# E-pico.net
KiCad netlist of a schematic drawn in Altium Designer
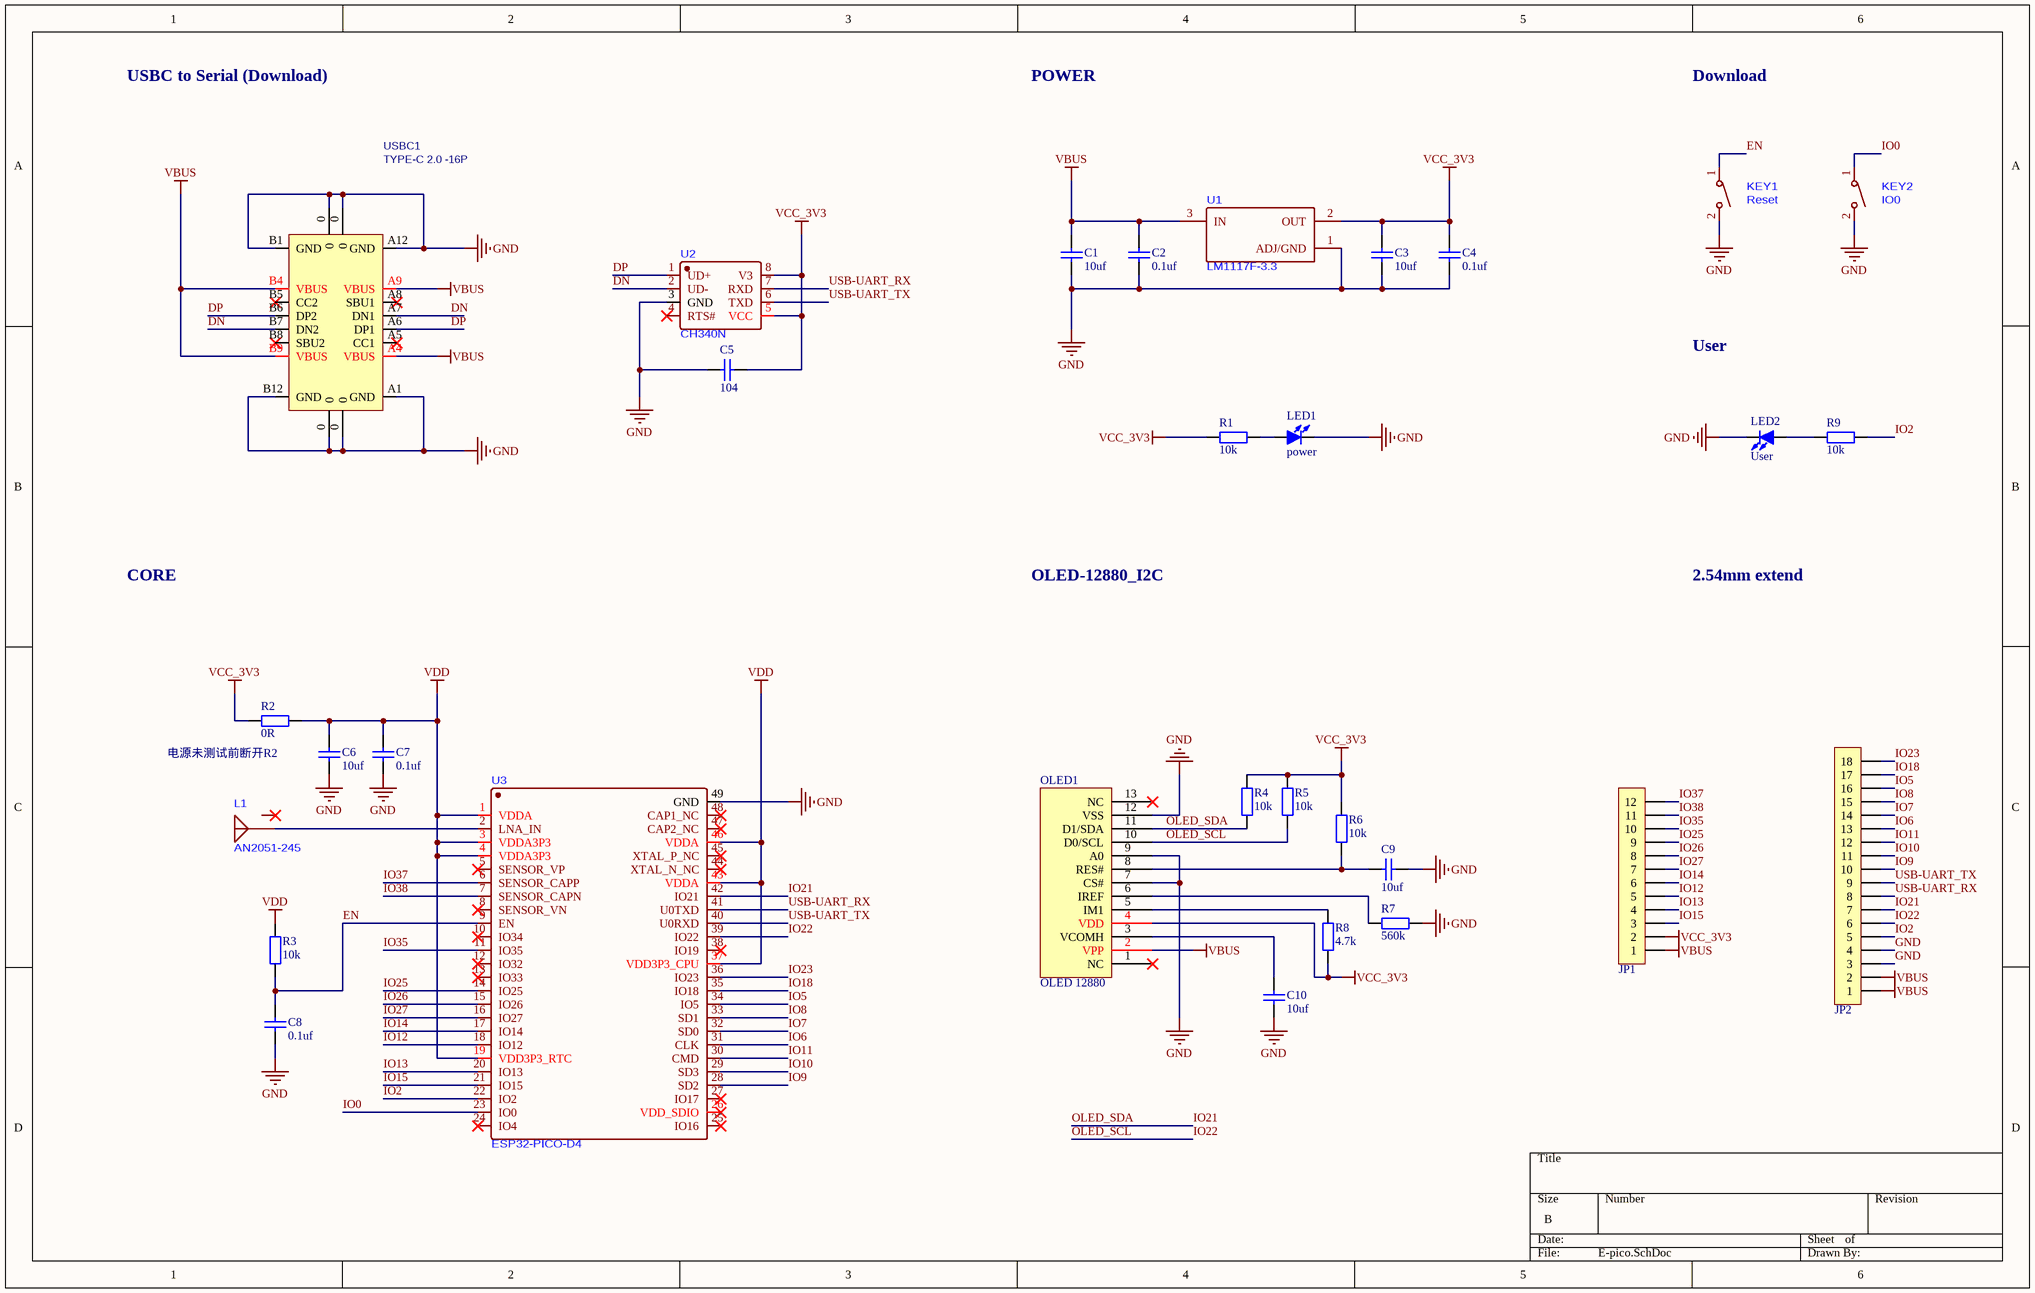
[diagram p0: E-pico.SchDoc]

(export (version "E")
  (design (tool "Eeschema 10.0.6"))
  (components
    (comp (ref "C1")
      (value "10uf")
      (footprint "C0603_M")
      (description "贴片电容/MLCC电容")
      (libsource (lib "0.1 - 电阻-电容-电感-晶振-晶体-磁珠-电位器-法拉电容-馈通电容") (part "C"))
    )
    (comp (ref "C2")
      (value "0.1uf")
      (footprint "C0603_M")
      (description "贴片电容/MLCC电容")
      (libsource (lib "0.1 - 电阻-电容-电感-晶振-晶体-磁珠-电位器-法拉电容-馈通电容") (part "C"))
    )
    (comp (ref "C3")
      (value "10uf")
      (footprint "C0603_M")
      (description "贴片电容/MLCC电容")
      (libsource (lib "0.1 - 电阻-电容-电感-晶振-晶体-磁珠-电位器-法拉电容-馈通电容") (part "C"))
    )
    (comp (ref "C4")
      (value "0.1uf")
      (footprint "C0603_M")
      (description "贴片电容/MLCC电容")
      (libsource (lib "0.1 - 电阻-电容-电感-晶振-晶体-磁珠-电位器-法拉电容-馈通电容") (part "C"))
    )
    (comp (ref "C5")
      (value "104")
      (footprint "C0603_M")
      (description "贴片电容/MLCC电容")
      (libsource (lib "0.1 - 电阻-电容-电感-晶振-晶体-磁珠-电位器-法拉电容-馈通电容") (part "C"))
    )
    (comp (ref "C6")
      (value "10uf")
      (footprint "C0603_M")
      (description "贴片电容/MLCC电容")
      (libsource (lib "0.1 - 电阻-电容-电感-晶振-晶体-磁珠-电位器-法拉电容-馈通电容") (part "C"))
    )
    (comp (ref "C7")
      (value "0.1uf")
      (footprint "C0603_M")
      (description "贴片电容/MLCC电容")
      (libsource (lib "0.1 - 电阻-电容-电感-晶振-晶体-磁珠-电位器-法拉电容-馈通电容") (part "C"))
    )
    (comp (ref "C8")
      (value "0.1uf")
      (footprint "C0603_M")
      (description "贴片电容/MLCC电容")
      (libsource (lib "0.1 - 电阻-电容-电感-晶振-晶体-磁珠-电位器-法拉电容-馈通电容") (part "C"))
    )
    (comp (ref "C9")
      (value "10uf")
      (footprint "C0603_M")
      (description "贴片电容/MLCC电容")
      (libsource (lib "0.1 - 电阻-电容-电感-晶振-晶体-磁珠-电位器-法拉电容-馈通电容") (part "C"))
    )
    (comp (ref "C10")
      (value "10uf")
      (footprint "C0603_M")
      (description "贴片电容/MLCC电容")
      (libsource (lib "0.1 - 电阻-电容-电感-晶振-晶体-磁珠-电位器-法拉电容-馈通电容") (part "C"))
    )
    (comp (ref "JP1")
      (value "HDR-1X12")
      (footprint "HDR2.54-LI-12P")
      (description "12P接插件")
      (libsource (lib "5.5 - 2.54mm连接器(KF2EDGK_XH2.54_2.54排针排母)") (part "Header 12"))
    )
    (comp (ref "JP2")
      (value "HDR-1X18")
      (footprint "HDR2.54-LI-18P")
      (description "18P接插件")
      (libsource (lib "5.5 - 2.54mm连接器(KF2EDGK_XH2.54_2.54排针排母)") (part "Header 18"))
    )
    (comp (ref "KEY1")
      (value "Reset")
      (footprint "SW-SMD_ST-1186S")
      (description "C589199")
      (libsource (lib "E-pico") (part "侧按小龟ST-1186S"))
    )
    (comp (ref "KEY2")
      (value "IO0")
      (footprint "SW-SMD_ST-1186S")
      (description "C589199")
      (libsource (lib "E-pico") (part "侧按小龟ST-1186S"))
    )
    (comp (ref "L1")
      (value "AN2051-245")
      (footprint "ANT2051")
      (libsource (lib "E-pico") (part "AN2051-245"))
    )
    (comp (ref "LED1")
      (value "power")
      (footprint "LED0603_Y")
      (description "贴片LED")
      (libsource (lib "0.3 - LED发光二极管-IR二极管_接收管-光耦") (part "LED-SMD"))
    )
    (comp (ref "LED2")
      (value "User")
      (footprint "LED0603_Y")
      (description "贴片LED")
      (libsource (lib "0.3 - LED发光二极管-IR二极管_接收管-光耦") (part "LED-SMD"))
    )
    (comp (ref "OLED1")
      (value "OLED 12880")
      (footprint "0.78'OLED-12880-13pin-short")
      (libsource (lib "E-pico") (part "0.78寸12880oled"))
    )
    (comp (ref "R1")
      (value "10k")
      (footprint "R0603_M")
      (description "贴片电阻")
      (libsource (lib "0.1 - 电阻-电容-电感-晶振-晶体-磁珠-电位器-法拉电容-馈通电容") (part "R"))
    )
    (comp (ref "R2")
      (value "0R")
      (footprint "R0603_M")
      (description "贴片电阻")
      (libsource (lib "0.1 - 电阻-电容-电感-晶振-晶体-磁珠-电位器-法拉电容-馈通电容") (part "R"))
    )
    (comp (ref "R3")
      (value "10k")
      (footprint "R0603_M")
      (description "贴片电阻")
      (libsource (lib "0.1 - 电阻-电容-电感-晶振-晶体-磁珠-电位器-法拉电容-馈通电容") (part "R"))
    )
    (comp (ref "R4")
      (value "10k")
      (footprint "R0603_M")
      (description "贴片电阻")
      (libsource (lib "0.1 - 电阻-电容-电感-晶振-晶体-磁珠-电位器-法拉电容-馈通电容") (part "R"))
    )
    (comp (ref "R5")
      (value "10k")
      (footprint "R0603_M")
      (description "贴片电阻")
      (libsource (lib "0.1 - 电阻-电容-电感-晶振-晶体-磁珠-电位器-法拉电容-馈通电容") (part "R"))
    )
    (comp (ref "R6")
      (value "10k")
      (footprint "R0603_M")
      (description "贴片电阻")
      (libsource (lib "0.1 - 电阻-电容-电感-晶振-晶体-磁珠-电位器-法拉电容-馈通电容") (part "R"))
    )
    (comp (ref "R7")
      (value "560k")
      (footprint "R0603_M")
      (description "贴片电阻")
      (libsource (lib "0.1 - 电阻-电容-电感-晶振-晶体-磁珠-电位器-法拉电容-馈通电容") (part "R"))
    )
    (comp (ref "R8")
      (value "4.7k")
      (footprint "R0603_M")
      (description "贴片电阻")
      (libsource (lib "0.1 - 电阻-电容-电感-晶振-晶体-磁珠-电位器-法拉电容-馈通电容") (part "R"))
    )
    (comp (ref "R9")
      (value "10k")
      (footprint "R0603_M")
      (description "贴片电阻")
      (libsource (lib "0.1 - 电阻-电容-电感-晶振-晶体-磁珠-电位器-法拉电容-馈通电容") (part "R"))
    )
    (comp (ref "U1")
      (value "LM1117F-3.3")
      (footprint "SOT89-150P410X160-3N")
      (libsource (lib "E-pico") (part "LM1117F-3.3"))
    )
    (comp (ref "U2")
      (value "CH340N")
      (footprint "SOP-8_L5.0-W4.0-P1.27-LS6.0-BL")
      (libsource (lib "E-pico") (part "CH340N"))
    )
    (comp (ref "U3")
      (value "ESP32-PICO-D4")
      (footprint "QFN-48_L7.0-W7.0-P0.50-BL-EP5.4")
      (libsource (lib "E-pico") (part "ESP32-PICO-D4"))
    )
    (comp (ref "USBC1")
      (value "TYPE-C 2.0 -16P")
      (footprint "USB-C-SMD_16P")
      (description "USB2.0_Type-C_16Pin母座")
      (libsource (lib "0.6 - 电源-以太网-音频-Type-C USB插座") (part "USB2.0_Type-C_16Pin"))
    )
  )
  (nets
    (net (code "1") (name "/DN") (class "Default")
      (node (ref "U2") (pin "2") (pinfunction "UD-_2") (pintype "passive"))
      (node (ref "USBC1") (pin "A7") (pinfunction "DN1_A7") (pintype "passive"))
      (node (ref "USBC1") (pin "B7") (pinfunction "DN2_B7") (pintype "passive"))
    )
    (net (code "2") (name "/DP") (class "Default")
      (node (ref "U2") (pin "1") (pinfunction "UD+_1") (pintype "passive"))
      (node (ref "USBC1") (pin "A6") (pinfunction "DP1_A6") (pintype "passive"))
      (node (ref "USBC1") (pin "B6") (pinfunction "DP2_B6") (pintype "passive"))
    )
    (net (code "3") (name "/EN") (class "Default")
      (node (ref "C8") (pin "2") (pinfunction "2_2") (pintype "passive"))
      (node (ref "KEY1") (pin "1") (pinfunction "1_1") (pintype "passive"))
      (node (ref "R3") (pin "2") (pinfunction "2_2") (pintype "passive"))
      (node (ref "U3") (pin "9") (pinfunction "EN_9") (pintype "passive"))
    )
    (net (code "4") (name "/IO0") (class "Default")
      (node (ref "KEY2") (pin "1") (pinfunction "1_1") (pintype "passive"))
      (node (ref "U3") (pin "23") (pinfunction "IO0_23") (pintype "passive"))
    )
    (net (code "5") (name "/IO2") (class "Default")
      (node (ref "JP2") (pin "5") (pinfunction "5_5") (pintype "passive"))
      (node (ref "R9") (pin "1") (pinfunction "1_1") (pintype "passive"))
      (node (ref "U3") (pin "22") (pinfunction "IO2_22") (pintype "passive"))
    )
    (net (code "6") (name "/IO5") (class "Default")
      (node (ref "JP2") (pin "16") (pinfunction "16_16") (pintype "passive"))
      (node (ref "U3") (pin "34") (pinfunction "IO5_34") (pintype "passive"))
    )
    (net (code "7") (name "/IO6") (class "Default")
      (node (ref "JP2") (pin "13") (pinfunction "13_13") (pintype "passive"))
      (node (ref "U3") (pin "31") (pinfunction "CLK_31") (pintype "passive"))
    )
    (net (code "8") (name "/IO7") (class "Default")
      (node (ref "JP2") (pin "14") (pinfunction "14_14") (pintype "passive"))
      (node (ref "U3") (pin "32") (pinfunction "SD0_32") (pintype "passive"))
    )
    (net (code "9") (name "/IO8") (class "Default")
      (node (ref "JP2") (pin "15") (pinfunction "15_15") (pintype "passive"))
      (node (ref "U3") (pin "33") (pinfunction "SD1_33") (pintype "passive"))
    )
    (net (code "10") (name "/IO9") (class "Default")
      (node (ref "JP2") (pin "10") (pinfunction "10_10") (pintype "passive"))
      (node (ref "U3") (pin "28") (pinfunction "SD2_28") (pintype "passive"))
    )
    (net (code "11") (name "/IO10") (class "Default")
      (node (ref "JP2") (pin "11") (pinfunction "11_11") (pintype "passive"))
      (node (ref "U3") (pin "29") (pinfunction "SD3_29") (pintype "passive"))
    )
    (net (code "12") (name "/IO11") (class "Default")
      (node (ref "JP2") (pin "12") (pinfunction "12_12") (pintype "passive"))
      (node (ref "U3") (pin "30") (pinfunction "CMD_30") (pintype "passive"))
    )
    (net (code "13") (name "/IO12") (class "Default")
      (node (ref "JP1") (pin "5") (pinfunction "5_5") (pintype "passive"))
      (node (ref "U3") (pin "18") (pinfunction "IO12_18") (pintype "passive"))
    )
    (net (code "14") (name "/IO13") (class "Default")
      (node (ref "JP1") (pin "4") (pinfunction "4_4") (pintype "passive"))
      (node (ref "U3") (pin "20") (pinfunction "IO13_20") (pintype "passive"))
    )
    (net (code "15") (name "/IO14") (class "Default")
      (node (ref "JP1") (pin "6") (pinfunction "6_6") (pintype "passive"))
      (node (ref "U3") (pin "17") (pinfunction "IO14_17") (pintype "passive"))
    )
    (net (code "16") (name "/IO15") (class "Default")
      (node (ref "JP1") (pin "3") (pinfunction "3_3") (pintype "passive"))
      (node (ref "U3") (pin "21") (pinfunction "IO15_21") (pintype "passive"))
    )
    (net (code "17") (name "/IO18") (class "Default")
      (node (ref "JP2") (pin "17") (pinfunction "17_17") (pintype "passive"))
      (node (ref "U3") (pin "35") (pinfunction "IO18_35") (pintype "passive"))
    )
    (net (code "18") (name "/IO21") (class "Default")
      (node (ref "JP2") (pin "7") (pinfunction "7_7") (pintype "passive"))
      (node (ref "OLED1") (pin "11") (pinfunction "D1/SDA_11") (pintype "passive"))
      (node (ref "R4") (pin "2") (pinfunction "2_2") (pintype "passive"))
      (node (ref "U3") (pin "42") (pinfunction "IO21_42") (pintype "passive"))
    )
    (net (code "19") (name "/IO22") (class "Default")
      (node (ref "JP2") (pin "6") (pinfunction "6_6") (pintype "passive"))
      (node (ref "OLED1") (pin "10") (pinfunction "D0/SCL_10") (pintype "passive"))
      (node (ref "R5") (pin "2") (pinfunction "2_2") (pintype "passive"))
      (node (ref "U3") (pin "39") (pinfunction "IO22_39") (pintype "passive"))
    )
    (net (code "20") (name "/IO23") (class "Default")
      (node (ref "JP2") (pin "18") (pinfunction "18_18") (pintype "passive"))
      (node (ref "U3") (pin "36") (pinfunction "IO23_36") (pintype "passive"))
    )
    (net (code "21") (name "/IO25") (class "Default")
      (node (ref "JP1") (pin "9") (pinfunction "9_9") (pintype "passive"))
      (node (ref "U3") (pin "14") (pinfunction "IO25_14") (pintype "passive"))
    )
    (net (code "22") (name "/IO26") (class "Default")
      (node (ref "JP1") (pin "8") (pinfunction "8_8") (pintype "passive"))
      (node (ref "U3") (pin "15") (pinfunction "IO26_15") (pintype "passive"))
    )
    (net (code "23") (name "/IO27") (class "Default")
      (node (ref "JP1") (pin "7") (pinfunction "7_7") (pintype "passive"))
      (node (ref "U3") (pin "16") (pinfunction "IO27_16") (pintype "passive"))
    )
    (net (code "24") (name "/IO35") (class "Default")
      (node (ref "JP1") (pin "10") (pinfunction "10_10") (pintype "passive"))
      (node (ref "U3") (pin "11") (pinfunction "IO35_11") (pintype "passive"))
    )
    (net (code "25") (name "/IO37") (class "Default")
      (node (ref "JP1") (pin "12") (pinfunction "12_12") (pintype "passive"))
      (node (ref "U3") (pin "6") (pinfunction "SENSOR_CAPP_6") (pintype "passive"))
    )
    (net (code "26") (name "/IO38") (class "Default")
      (node (ref "JP1") (pin "11") (pinfunction "11_11") (pintype "passive"))
      (node (ref "U3") (pin "7") (pinfunction "SENSOR_CAPN_7") (pintype "passive"))
    )
    (net (code "27") (name "/USB-UART_RX") (class "Default")
      (node (ref "JP2") (pin "8") (pinfunction "8_8") (pintype "passive"))
      (node (ref "U2") (pin "7") (pinfunction "RXD_7") (pintype "passive"))
      (node (ref "U3") (pin "41") (pinfunction "U0TXD_41") (pintype "passive"))
    )
    (net (code "28") (name "/USB-UART_TX") (class "Default")
      (node (ref "JP2") (pin "9") (pinfunction "9_9") (pintype "passive"))
      (node (ref "U2") (pin "6") (pinfunction "TXD_6") (pintype "passive"))
      (node (ref "U3") (pin "40") (pinfunction "U0RXD_40") (pintype "passive"))
    )
    (net (code "29") (name "GND") (class "Default")
      (node (ref "C1") (pin "2") (pinfunction "2_2") (pintype "passive"))
      (node (ref "C10") (pin "1") (pinfunction "1_1") (pintype "passive"))
      (node (ref "C2") (pin "2") (pinfunction "2_2") (pintype "passive"))
      (node (ref "C3") (pin "2") (pinfunction "2_2") (pintype "passive"))
      (node (ref "C4") (pin "2") (pinfunction "2_2") (pintype "passive"))
      (node (ref "C5") (pin "1") (pinfunction "1_1") (pintype "passive"))
      (node (ref "C6") (pin "1") (pinfunction "1_1") (pintype "passive"))
      (node (ref "C7") (pin "1") (pinfunction "1_1") (pintype "passive"))
      (node (ref "C8") (pin "1") (pinfunction "1_1") (pintype "passive"))
      (node (ref "C9") (pin "1") (pinfunction "1_1") (pintype "passive"))
      (node (ref "JP2") (pin "3") (pinfunction "3_3") (pintype "passive"))
      (node (ref "JP2") (pin "4") (pinfunction "4_4") (pintype "passive"))
      (node (ref "KEY1") (pin "2") (pinfunction "2_2") (pintype "passive"))
      (node (ref "KEY2") (pin "2") (pinfunction "2_2") (pintype "passive"))
      (node (ref "LED1") (pin "2") (pinfunction "K_2") (pintype "passive"))
      (node (ref "LED2") (pin "2") (pinfunction "K_2") (pintype "passive"))
      (node (ref "OLED1") (pin "12") (pinfunction "VSS_12") (pintype "passive"))
      (node (ref "OLED1") (pin "7") (pinfunction "CS#_7") (pintype "passive"))
      (node (ref "OLED1") (pin "9") (pinfunction "A0_9") (pintype "passive"))
      (node (ref "R7") (pin "1") (pinfunction "1_1") (pintype "passive"))
      (node (ref "U1") (pin "1") (pinfunction "ADJ/GND_1") (pintype "passive"))
      (node (ref "U2") (pin "3") (pinfunction "GND_3") (pintype "passive"))
      (node (ref "U3") (pin "49") (pinfunction "GND_49") (pintype "passive"))
      (node (ref "USBC1") (pin "0") (pinfunction "0_0") (pintype "passive"))
      (node (ref "USBC1") (pin "A1") (pinfunction "GND_A1") (pintype "passive"))
      (node (ref "USBC1") (pin "A12") (pinfunction "GND_A12") (pintype "passive"))
      (node (ref "USBC1") (pin "B1") (pinfunction "GND_B1") (pintype "passive"))
      (node (ref "USBC1") (pin "B12") (pinfunction "GND_B12") (pintype "passive"))
    )
    (net (code "30") (name "Net-(L1-ANT)") (class "Default")
      (node (ref "L1") (pin "1") (pinfunction "ANT_1") (pintype "passive"))
      (node (ref "U3") (pin "2") (pinfunction "LNA_IN_2") (pintype "passive"))
    )
    (net (code "31") (name "Net-(LED1-A)") (class "Default")
      (node (ref "LED1") (pin "1") (pinfunction "A_1") (pintype "passive"))
      (node (ref "R1") (pin "2") (pinfunction "2_2") (pintype "passive"))
    )
    (net (code "32") (name "Net-(LED2-A)") (class "Default")
      (node (ref "LED2") (pin "1") (pinfunction "A_1") (pintype "passive"))
      (node (ref "R9") (pin "2") (pinfunction "2_2") (pintype "passive"))
    )
    (net (code "33") (name "Net-(OLED1-IM1)") (class "Default")
      (node (ref "OLED1") (pin "5") (pinfunction "IM1_5") (pintype "passive"))
      (node (ref "R8") (pin "2") (pinfunction "2_2") (pintype "passive"))
    )
    (net (code "34") (name "Net-(OLED1-IREF)") (class "Default")
      (node (ref "OLED1") (pin "6") (pinfunction "IREF_6") (pintype "passive"))
      (node (ref "R7") (pin "2") (pinfunction "2_2") (pintype "passive"))
    )
    (net (code "35") (name "Net-(OLED1-RES#)") (class "Default")
      (node (ref "C9") (pin "2") (pinfunction "2_2") (pintype "passive"))
      (node (ref "OLED1") (pin "8") (pinfunction "RES#_8") (pintype "passive"))
      (node (ref "R6") (pin "2") (pinfunction "2_2") (pintype "passive"))
    )
    (net (code "36") (name "Net-(OLED1-VCOMH)") (class "Default")
      (node (ref "C10") (pin "2") (pinfunction "2_2") (pintype "passive"))
      (node (ref "OLED1") (pin "3") (pinfunction "VCOMH_3") (pintype "passive"))
    )
    (net (code "37") (name "VBUS") (class "Default")
      (node (ref "C1") (pin "1") (pinfunction "1_1") (pintype "passive"))
      (node (ref "C2") (pin "1") (pinfunction "1_1") (pintype "passive"))
      (node (ref "JP1") (pin "1") (pinfunction "1_1") (pintype "passive"))
      (node (ref "JP2") (pin "1") (pinfunction "1_1") (pintype "passive"))
      (node (ref "JP2") (pin "2") (pinfunction "2_2") (pintype "passive"))
      (node (ref "OLED1") (pin "2") (pinfunction "VPP_2") (pintype "passive"))
      (node (ref "U1") (pin "3") (pinfunction "IN_3") (pintype "passive"))
      (node (ref "USBC1") (pin "A4") (pinfunction "VBUS_A4") (pintype "passive"))
      (node (ref "USBC1") (pin "A9") (pinfunction "VBUS_A9") (pintype "passive"))
      (node (ref "USBC1") (pin "B4") (pinfunction "VBUS_B4") (pintype "passive"))
      (node (ref "USBC1") (pin "B9") (pinfunction "VBUS_B9") (pintype "passive"))
    )
    (net (code "38") (name "VCC_3V3") (class "Default")
      (node (ref "C3") (pin "1") (pinfunction "1_1") (pintype "passive"))
      (node (ref "C4") (pin "1") (pinfunction "1_1") (pintype "passive"))
      (node (ref "C5") (pin "2") (pinfunction "2_2") (pintype "passive"))
      (node (ref "JP1") (pin "2") (pinfunction "2_2") (pintype "passive"))
      (node (ref "OLED1") (pin "4") (pinfunction "VDD_4") (pintype "passive"))
      (node (ref "R1") (pin "1") (pinfunction "1_1") (pintype "passive"))
      (node (ref "R2") (pin "1") (pinfunction "1_1") (pintype "passive"))
      (node (ref "R4") (pin "1") (pinfunction "1_1") (pintype "passive"))
      (node (ref "R5") (pin "1") (pinfunction "1_1") (pintype "passive"))
      (node (ref "R6") (pin "1") (pinfunction "1_1") (pintype "passive"))
      (node (ref "R8") (pin "1") (pinfunction "1_1") (pintype "passive"))
      (node (ref "U1") (pin "2") (pinfunction "OUT_2") (pintype "passive"))
      (node (ref "U2") (pin "5") (pinfunction "VCC_5") (pintype "passive"))
      (node (ref "U2") (pin "8") (pinfunction "V3_8") (pintype "passive"))
    )
    (net (code "39") (name "VDD") (class "Default")
      (node (ref "C6") (pin "2") (pinfunction "2_2") (pintype "passive"))
      (node (ref "C7") (pin "2") (pinfunction "2_2") (pintype "passive"))
      (node (ref "R2") (pin "2") (pinfunction "2_2") (pintype "passive"))
      (node (ref "R3") (pin "1") (pinfunction "1_1") (pintype "passive"))
      (node (ref "U3") (pin "1") (pinfunction "VDDA_1") (pintype "passive"))
      (node (ref "U3") (pin "19") (pinfunction "VDD3P3_RTC_19") (pintype "passive"))
      (node (ref "U3") (pin "3") (pinfunction "VDDA3P3_3") (pintype "passive"))
      (node (ref "U3") (pin "37") (pinfunction "VDD3P3_CPU_37") (pintype "passive"))
      (node (ref "U3") (pin "4") (pinfunction "VDDA3P3_4") (pintype "passive"))
      (node (ref "U3") (pin "43") (pinfunction "VDDA_43") (pintype "passive"))
      (node (ref "U3") (pin "46") (pinfunction "VDDA_46") (pintype "passive"))
    )
    (net (code "40") (name "unconnected-(L1-Pad2)") (class "Default")
      (node (ref "L1") (pin "2") (pinfunction "2_2") (pintype "passive+no_connect"))
    )
    (net (code "41") (name "unconnected-(OLED1-NC-Pad1)") (class "Default")
      (node (ref "OLED1") (pin "1") (pinfunction "NC_1") (pintype "passive+no_connect"))
    )
    (net (code "42") (name "unconnected-(OLED1-NC-Pad13)") (class "Default")
      (node (ref "OLED1") (pin "13") (pinfunction "NC_13") (pintype "passive+no_connect"))
    )
    (net (code "43") (name "unconnected-(U2-RTS#-Pad4)") (class "Default")
      (node (ref "U2") (pin "4") (pinfunction "RTS#_4") (pintype "passive+no_connect"))
    )
    (net (code "44") (name "unconnected-(U3-CAP1_NC-Pad48)") (class "Default")
      (node (ref "U3") (pin "48") (pinfunction "CAP1_NC_48") (pintype "passive+no_connect"))
    )
    (net (code "45") (name "unconnected-(U3-CAP2_NC-Pad47)") (class "Default")
      (node (ref "U3") (pin "47") (pinfunction "CAP2_NC_47") (pintype "passive+no_connect"))
    )
    (net (code "46") (name "unconnected-(U3-IO4-Pad24)") (class "Default")
      (node (ref "U3") (pin "24") (pinfunction "IO4_24") (pintype "passive+no_connect"))
    )
    (net (code "47") (name "unconnected-(U3-IO16-Pad25)") (class "Default")
      (node (ref "U3") (pin "25") (pinfunction "IO16_25") (pintype "passive+no_connect"))
    )
    (net (code "48") (name "unconnected-(U3-IO17-Pad27)") (class "Default")
      (node (ref "U3") (pin "27") (pinfunction "IO17_27") (pintype "passive+no_connect"))
    )
    (net (code "49") (name "unconnected-(U3-IO19-Pad38)") (class "Default")
      (node (ref "U3") (pin "38") (pinfunction "IO19_38") (pintype "passive+no_connect"))
    )
    (net (code "50") (name "unconnected-(U3-IO32-Pad12)") (class "Default")
      (node (ref "U3") (pin "12") (pinfunction "IO32_12") (pintype "passive+no_connect"))
    )
    (net (code "51") (name "unconnected-(U3-IO33-Pad13)") (class "Default")
      (node (ref "U3") (pin "13") (pinfunction "IO33_13") (pintype "passive+no_connect"))
    )
    (net (code "52") (name "unconnected-(U3-IO34-Pad10)") (class "Default")
      (node (ref "U3") (pin "10") (pinfunction "IO34_10") (pintype "passive+no_connect"))
    )
    (net (code "53") (name "unconnected-(U3-SENSOR_VN-Pad8)") (class "Default")
      (node (ref "U3") (pin "8") (pinfunction "SENSOR_VN_8") (pintype "passive+no_connect"))
    )
    (net (code "54") (name "unconnected-(U3-SENSOR_VP-Pad5)") (class "Default")
      (node (ref "U3") (pin "5") (pinfunction "SENSOR_VP_5") (pintype "passive+no_connect"))
    )
    (net (code "55") (name "unconnected-(U3-VDD_SDIO-Pad26)") (class "Default")
      (node (ref "U3") (pin "26") (pinfunction "VDD_SDIO_26") (pintype "passive+no_connect"))
    )
    (net (code "56") (name "unconnected-(U3-XTAL_N_NC-Pad44)") (class "Default")
      (node (ref "U3") (pin "44") (pinfunction "XTAL_N_NC_44") (pintype "passive+no_connect"))
    )
    (net (code "57") (name "unconnected-(U3-XTAL_P_NC-Pad45)") (class "Default")
      (node (ref "U3") (pin "45") (pinfunction "XTAL_P_NC_45") (pintype "passive+no_connect"))
    )
    (net (code "58") (name "unconnected-(USBC1-CC1-PadA5)") (class "Default")
      (node (ref "USBC1") (pin "A5") (pinfunction "CC1_A5") (pintype "passive+no_connect"))
    )
    (net (code "59") (name "unconnected-(USBC1-CC2-PadB5)") (class "Default")
      (node (ref "USBC1") (pin "B5") (pinfunction "CC2_B5") (pintype "passive+no_connect"))
    )
    (net (code "60") (name "unconnected-(USBC1-SBU1-PadA8)") (class "Default")
      (node (ref "USBC1") (pin "A8") (pinfunction "SBU1_A8") (pintype "passive+no_connect"))
    )
    (net (code "61") (name "unconnected-(USBC1-SBU2-PadB8)") (class "Default")
      (node (ref "USBC1") (pin "B8") (pinfunction "SBU2_B8") (pintype "passive+no_connect"))
    )
  )
)
